# analog-daughter.net
KiCad netlist of a schematic drawn in EAGLE
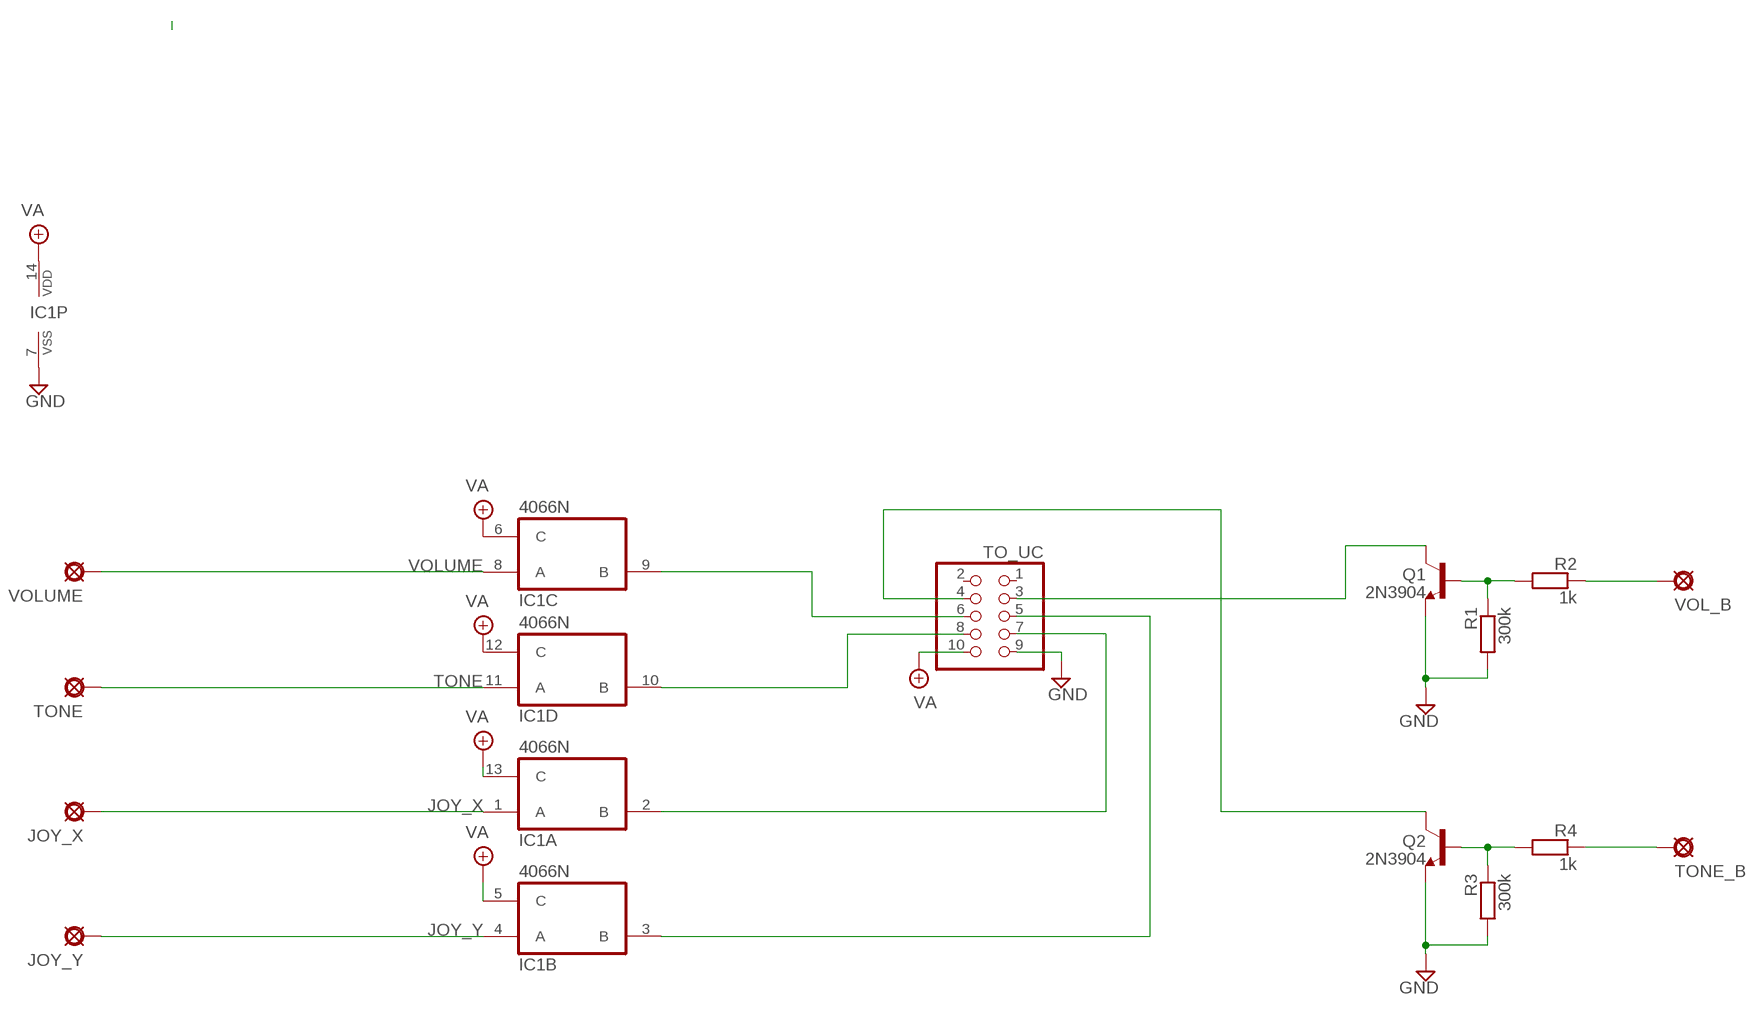
[diagram p0: schematic, sheet 1]

(export (version "E")
  (design (tool "Eeschema 10.0.6"))
  (components
    (comp (ref "IC1")
      (value "4066N")
      (footprint "eagle-import:DIL14")
      (libsource (lib "eagle-import") (part "4066N"))
    )
    (comp (ref "JOY_X")
      (value "PAD")
      (footprint "eagle-import:SQUARE")
      (libsource (lib "eagle-import") (part "PAD"))
    )
    (comp (ref "JOY_Y")
      (value "PAD")
      (footprint "eagle-import:SQUARE")
      (libsource (lib "eagle-import") (part "PAD"))
    )
    (comp (ref "Q1")
      (value "2N3904")
      (footprint "eagle-import:TO92-")
      (libsource (lib "eagle-import") (part "2N3904"))
    )
    (comp (ref "Q2")
      (value "2N3904")
      (footprint "eagle-import:TO92-")
      (libsource (lib "eagle-import") (part "2N3904"))
    )
    (comp (ref "R1")
      (value "300k")
      (footprint "eagle-import:R0207_1V")
      (libsource (lib "eagle-import") (part "6MM-EU1"))
    )
    (comp (ref "R2")
      (value "1k")
      (footprint "eagle-import:R0207_1V")
      (libsource (lib "eagle-import") (part "6MM-EU1"))
    )
    (comp (ref "R3")
      (value "300k")
      (footprint "eagle-import:R0207_1V")
      (libsource (lib "eagle-import") (part "6MM-EU1"))
    )
    (comp (ref "R4")
      (value "1k")
      (footprint "eagle-import:R0207_1V")
      (libsource (lib "eagle-import") (part "6MM-EU1"))
    )
    (comp (ref "TONE")
      (value "PAD")
      (footprint "eagle-import:SQUARE")
      (libsource (lib "eagle-import") (part "PAD"))
    )
    (comp (ref "TONE_B")
      (value "PAD")
      (footprint "eagle-import:SQUARE")
      (libsource (lib "eagle-import") (part "PAD"))
    )
    (comp (ref "TO_UC")
      (value "PINHD-2X5")
      (footprint "eagle-import:2X05")
      (libsource (lib "eagle-import") (part "PINHD-2X5"))
    )
    (comp (ref "VOLUME")
      (value "PAD")
      (footprint "eagle-import:SQUARE")
      (libsource (lib "eagle-import") (part "PAD"))
    )
    (comp (ref "VOL_B")
      (value "PAD")
      (footprint "eagle-import:SQUARE")
      (libsource (lib "eagle-import") (part "PAD"))
    )
  )
  (nets
    (net (code "1") (name "/JOY_X") (class "Default")
      (node (ref "IC1") (pin "1") (pinfunction "A_1") (pintype "tri_state"))
      (node (ref "JOY_X") (pin "1") (pinfunction "PAD_1") (pintype "passive"))
    )
    (net (code "2") (name "/JOY_Y") (class "Default")
      (node (ref "IC1") (pin "4") (pinfunction "A_4") (pintype "tri_state"))
      (node (ref "JOY_Y") (pin "1") (pinfunction "PAD_1") (pintype "passive"))
    )
    (net (code "3") (name "/TONE") (class "Default")
      (node (ref "IC1") (pin "11") (pinfunction "A_11") (pintype "tri_state"))
      (node (ref "TONE") (pin "1") (pinfunction "PAD_1") (pintype "passive"))
    )
    (net (code "4") (name "/VOLUME") (class "Default")
      (node (ref "IC1") (pin "8") (pinfunction "A_8") (pintype "tri_state"))
      (node (ref "VOLUME") (pin "1") (pinfunction "PAD_1") (pintype "passive"))
    )
    (net (code "5") (name "GND") (class "Default")
      (node (ref "IC1") (pin "7") (pinfunction "VSS_7") (pintype "power_in"))
      (node (ref "Q1") (pin "3") (pinfunction "E_3") (pintype "passive"))
      (node (ref "Q2") (pin "3") (pinfunction "E_3") (pintype "passive"))
      (node (ref "R1") (pin "2") (pinfunction "2_2") (pintype "passive"))
      (node (ref "R3") (pin "2") (pinfunction "2_2") (pintype "passive"))
      (node (ref "TO_UC") (pin "9") (pinfunction "9_9") (pintype "passive"))
    )
    (net (code "6") (name "Net-(IC1A-B)") (class "Default")
      (node (ref "IC1") (pin "2") (pinfunction "B_2") (pintype "tri_state"))
      (node (ref "TO_UC") (pin "7") (pinfunction "7_7") (pintype "passive"))
    )
    (net (code "7") (name "Net-(IC1B-B)") (class "Default")
      (node (ref "IC1") (pin "3") (pinfunction "B_3") (pintype "tri_state"))
      (node (ref "TO_UC") (pin "5") (pinfunction "5_5") (pintype "passive"))
    )
    (net (code "8") (name "Net-(IC1C-B)") (class "Default")
      (node (ref "IC1") (pin "9") (pinfunction "B_9") (pintype "tri_state"))
      (node (ref "TO_UC") (pin "6") (pinfunction "6_6") (pintype "passive"))
    )
    (net (code "9") (name "Net-(IC1D-B)") (class "Default")
      (node (ref "IC1") (pin "10") (pinfunction "B_10") (pintype "tri_state"))
      (node (ref "TO_UC") (pin "8") (pinfunction "8_8") (pintype "passive"))
    )
    (net (code "10") (name "Net-(Q1-B)") (class "Default")
      (node (ref "Q1") (pin "2") (pinfunction "B_2") (pintype "passive"))
      (node (ref "R1") (pin "1") (pinfunction "1_1") (pintype "passive"))
      (node (ref "R2") (pin "2") (pinfunction "2_2") (pintype "passive"))
    )
    (net (code "11") (name "Net-(Q1-C)") (class "Default")
      (node (ref "Q1") (pin "1") (pinfunction "C_1") (pintype "passive"))
      (node (ref "TO_UC") (pin "3") (pinfunction "3_3") (pintype "passive"))
    )
    (net (code "12") (name "Net-(Q2-B)") (class "Default")
      (node (ref "Q2") (pin "2") (pinfunction "B_2") (pintype "passive"))
      (node (ref "R3") (pin "1") (pinfunction "1_1") (pintype "passive"))
      (node (ref "R4") (pin "2") (pinfunction "2_2") (pintype "passive"))
    )
    (net (code "13") (name "Net-(Q2-C)") (class "Default")
      (node (ref "Q2") (pin "1") (pinfunction "C_1") (pintype "passive"))
      (node (ref "TO_UC") (pin "4") (pinfunction "4_4") (pintype "passive"))
    )
    (net (code "14") (name "Net-(TONE_B-PAD)") (class "Default")
      (node (ref "R4") (pin "1") (pinfunction "1_1") (pintype "passive"))
      (node (ref "TONE_B") (pin "1") (pinfunction "PAD_1") (pintype "passive"))
    )
    (net (code "15") (name "Net-(VOL_B-PAD)") (class "Default")
      (node (ref "R2") (pin "1") (pinfunction "1_1") (pintype "passive"))
      (node (ref "VOL_B") (pin "1") (pinfunction "PAD_1") (pintype "passive"))
    )
    (net (code "16") (name "VA") (class "Default")
      (node (ref "IC1") (pin "12") (pinfunction "C_12") (pintype "input"))
      (node (ref "IC1") (pin "13") (pinfunction "C_13") (pintype "input"))
      (node (ref "IC1") (pin "14") (pinfunction "VDD_14") (pintype "power_in"))
      (node (ref "IC1") (pin "5") (pinfunction "C_5") (pintype "input"))
      (node (ref "IC1") (pin "6") (pinfunction "C_6") (pintype "input"))
      (node (ref "TO_UC") (pin "10") (pinfunction "10_10") (pintype "passive"))
    )
    (net (code "17") (name "unconnected-(TO_UC-Pad1)") (class "Default")
      (node (ref "TO_UC") (pin "1") (pinfunction "1_1") (pintype "passive"))
    )
    (net (code "18") (name "unconnected-(TO_UC-Pad2)") (class "Default")
      (node (ref "TO_UC") (pin "2") (pinfunction "2_2") (pintype "passive"))
    )
  )
)
